# T-ShirtPress_Schematic.net
KiCad netlist of a schematic drawn in EAGLE
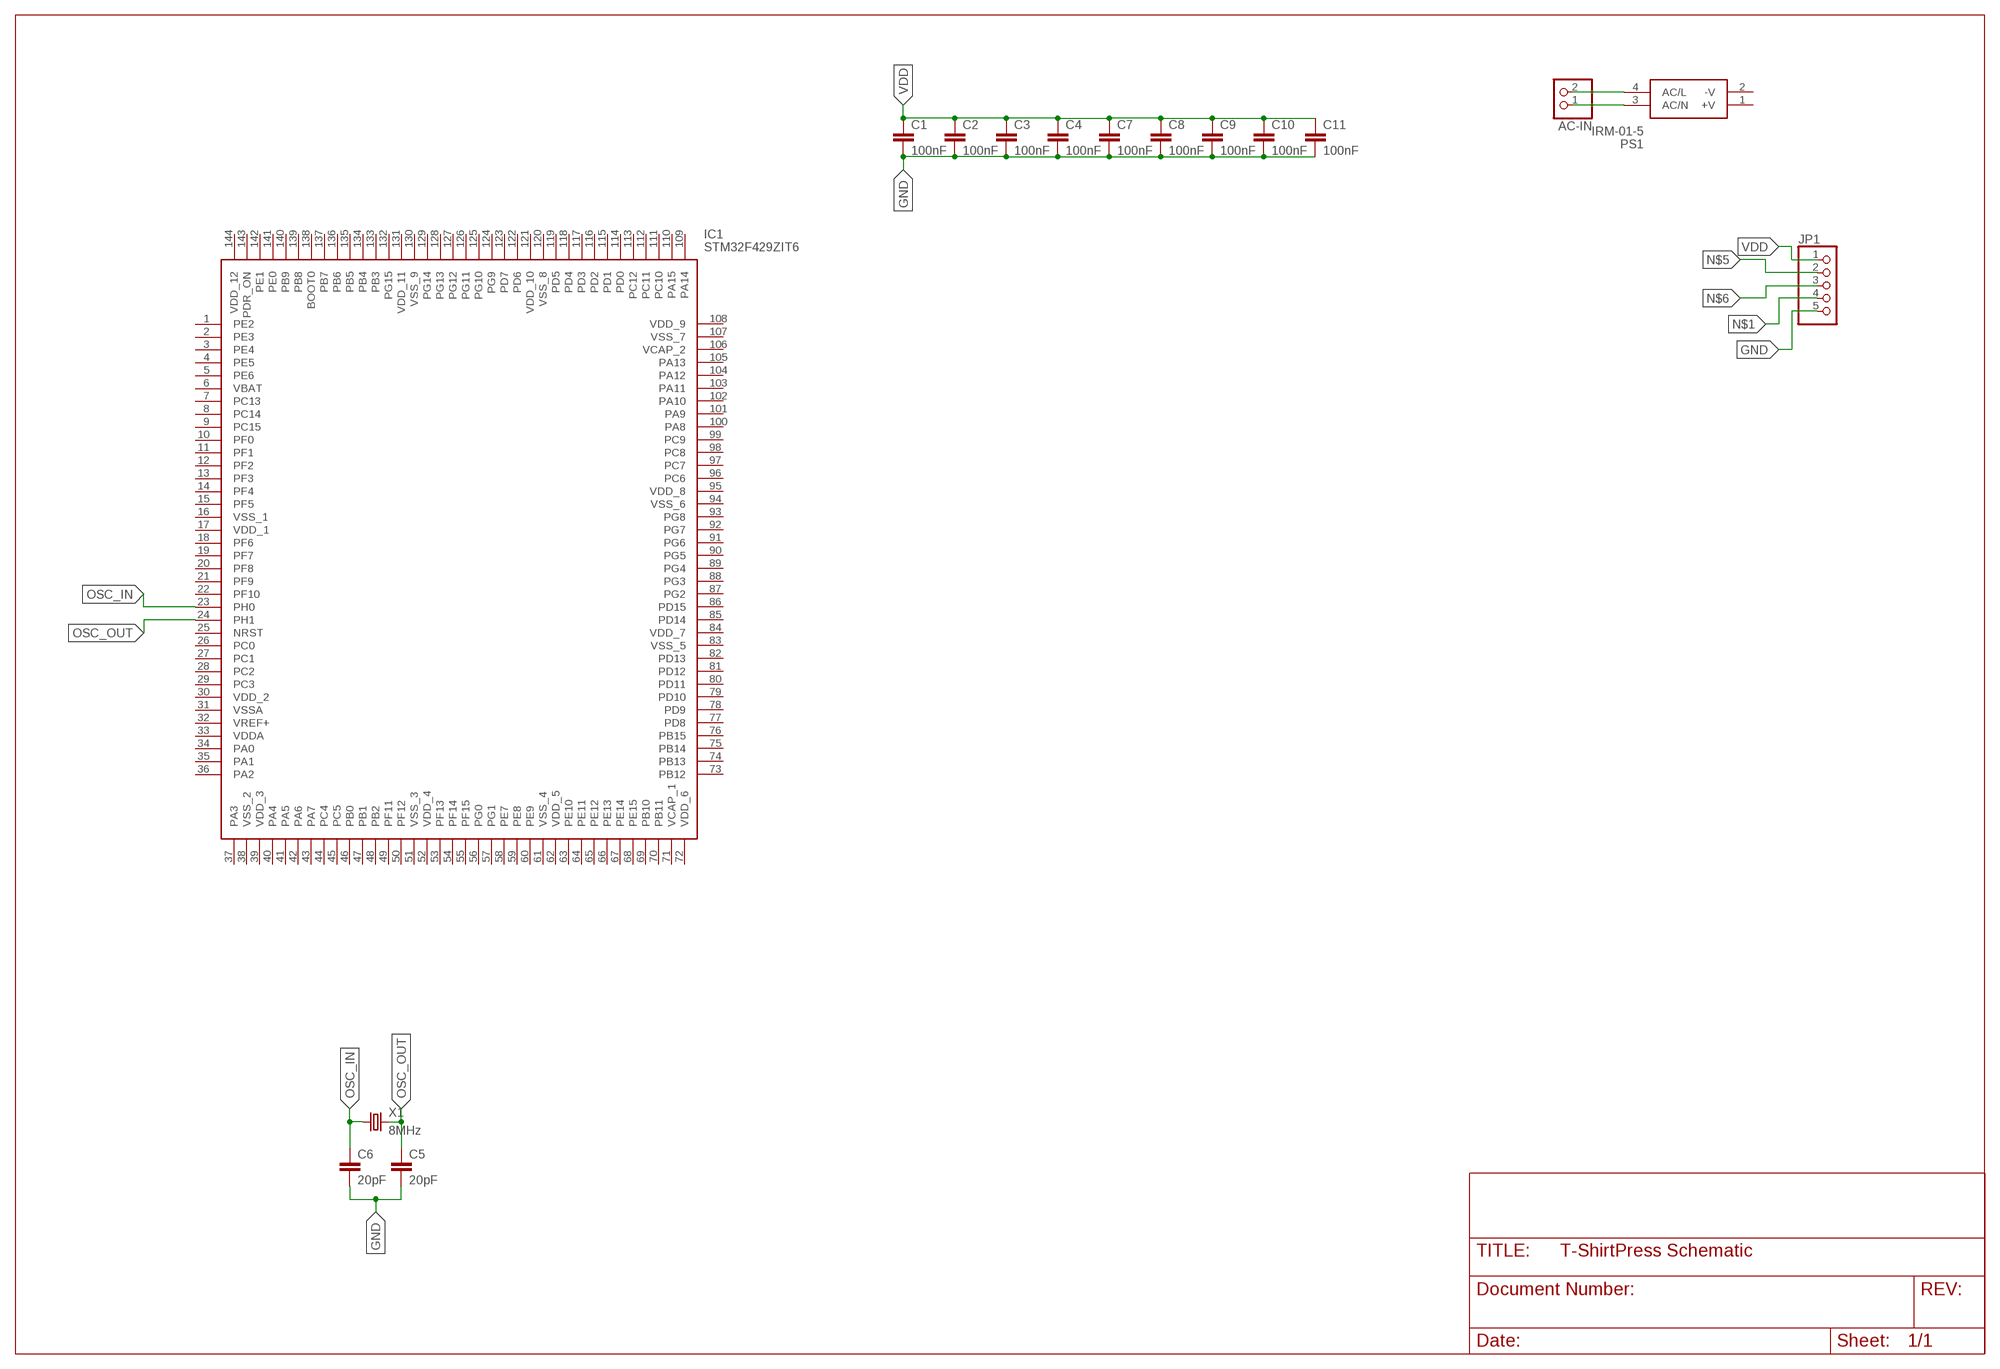
[diagram p0: schematic, sheet 1]

(export (version "E")
  (design (tool "Eeschema 10.0.6"))
  (components
    (comp (ref "AC-IN")
      (value "PINHD-1X2")
      (footprint "eagle-import:1X02")
      (libsource (lib "eagle-import") (part "PINHD-1X2"))
    )
    (comp (ref "C1")
      (value "100nF")
      (footprint "eagle-import:C1206")
      (libsource (lib "eagle-import") (part "C-EUC1206"))
    )
    (comp (ref "C2")
      (value "100nF")
      (footprint "eagle-import:C1206")
      (libsource (lib "eagle-import") (part "C-EUC1206"))
    )
    (comp (ref "C3")
      (value "100nF")
      (footprint "eagle-import:C1206")
      (libsource (lib "eagle-import") (part "C-EUC1206"))
    )
    (comp (ref "C4")
      (value "100nF")
      (footprint "eagle-import:C1206")
      (libsource (lib "eagle-import") (part "C-EUC1206"))
    )
    (comp (ref "C5")
      (value "20pF")
      (footprint "eagle-import:C1206")
      (libsource (lib "eagle-import") (part "C-EUC1206"))
    )
    (comp (ref "C6")
      (value "20pF")
      (footprint "eagle-import:C1206")
      (libsource (lib "eagle-import") (part "C-EUC1206"))
    )
    (comp (ref "C7")
      (value "100nF")
      (footprint "eagle-import:C1206")
      (libsource (lib "eagle-import") (part "C-EUC1206"))
    )
    (comp (ref "C8")
      (value "100nF")
      (footprint "eagle-import:C1206")
      (libsource (lib "eagle-import") (part "C-EUC1206"))
    )
    (comp (ref "C9")
      (value "100nF")
      (footprint "eagle-import:C1206")
      (libsource (lib "eagle-import") (part "C-EUC1206"))
    )
    (comp (ref "C10")
      (value "100nF")
      (footprint "eagle-import:C1206")
      (libsource (lib "eagle-import") (part "C-EUC1206"))
    )
    (comp (ref "C11")
      (value "100nF")
      (footprint "eagle-import:C1206")
      (libsource (lib "eagle-import") (part "C-EUC1206"))
    )
    (comp (ref "IC1")
      (value "STM32F429ZIT6")
      (footprint "eagle-import:QFP50P2200X2200X160-144N")
      (fields
        (field (name "MOUSER_PART_NUMBER") "511-STM32F429ZIT6")
        (field (name "RS_PART_NUMBER") "7926053P")
      )
      (libsource (lib "eagle-import") (part "STM32F429ZIT6"))
    )
    (comp (ref "JP1")
      (value "PINHD-1X5")
      (footprint "eagle-import:1X05")
      (libsource (lib "eagle-import") (part "PINHD-1X5"))
    )
    (comp (ref "PS1")
      (value "IRM-01-5")
      (footprint "eagle-import:IRM015")
      (fields (field (name "MOUSER_PART_NUMBER") "709-IRM01-5"))
      (libsource (lib "eagle-import") (part "IRM-01-5"))
    )
    (comp (ref "X1")
      (value "8MHz")
      (footprint "eagle-import:HC49_S")
      (libsource (lib "eagle-import") (part "CRYSTALHC49S"))
    )
  )
  (nets
    (net (code "1") (name "/VDDA") (class "Default")
      (node (ref "IC1") (pin "33") (pinfunction "VDDA_33") (pintype "power_in"))
    )
    (net (code "2") (name "/VDD_1") (class "Default")
      (node (ref "IC1") (pin "17") (pinfunction "VDD_1_17") (pintype "power_in"))
    )
    (net (code "3") (name "/VDD_2") (class "Default")
      (node (ref "IC1") (pin "30") (pinfunction "VDD_2_30") (pintype "power_in"))
    )
    (net (code "4") (name "/VDD_3") (class "Default")
      (node (ref "IC1") (pin "39") (pinfunction "VDD_3_39") (pintype "power_in"))
    )
    (net (code "5") (name "/VDD_4") (class "Default")
      (node (ref "IC1") (pin "52") (pinfunction "VDD_4_52") (pintype "power_in"))
    )
    (net (code "6") (name "/VDD_5") (class "Default")
      (node (ref "IC1") (pin "62") (pinfunction "VDD_5_62") (pintype "power_in"))
    )
    (net (code "7") (name "/VDD_6") (class "Default")
      (node (ref "IC1") (pin "72") (pinfunction "VDD_6_72") (pintype "power_in"))
    )
    (net (code "8") (name "/VDD_7") (class "Default")
      (node (ref "IC1") (pin "84") (pinfunction "VDD_7_84") (pintype "power_in"))
    )
    (net (code "9") (name "/VDD_8") (class "Default")
      (node (ref "IC1") (pin "95") (pinfunction "VDD_8_95") (pintype "power_in"))
    )
    (net (code "10") (name "/VDD_9") (class "Default")
      (node (ref "IC1") (pin "108") (pinfunction "VDD_9_108") (pintype "power_in"))
    )
    (net (code "11") (name "/VDD_10") (class "Default")
      (node (ref "IC1") (pin "121") (pinfunction "VDD_10_121") (pintype "power_in"))
    )
    (net (code "12") (name "/VDD_11") (class "Default")
      (node (ref "IC1") (pin "131") (pinfunction "VDD_11_131") (pintype "power_in"))
    )
    (net (code "13") (name "/VDD_12") (class "Default")
      (node (ref "IC1") (pin "144") (pinfunction "VDD_12_144") (pintype "power_in"))
    )
    (net (code "14") (name "/VSSA") (class "Default")
      (node (ref "IC1") (pin "31") (pinfunction "VSSA_31") (pintype "power_in"))
    )
    (net (code "15") (name "/VSS_1") (class "Default")
      (node (ref "IC1") (pin "16") (pinfunction "VSS_1_16") (pintype "power_in"))
    )
    (net (code "16") (name "/VSS_2") (class "Default")
      (node (ref "IC1") (pin "38") (pinfunction "VSS_2_38") (pintype "power_in"))
    )
    (net (code "17") (name "/VSS_3") (class "Default")
      (node (ref "IC1") (pin "51") (pinfunction "VSS_3_51") (pintype "power_in"))
    )
    (net (code "18") (name "/VSS_4") (class "Default")
      (node (ref "IC1") (pin "61") (pinfunction "VSS_4_61") (pintype "power_in"))
    )
    (net (code "19") (name "/VSS_5") (class "Default")
      (node (ref "IC1") (pin "83") (pinfunction "VSS_5_83") (pintype "power_in"))
    )
    (net (code "20") (name "/VSS_6") (class "Default")
      (node (ref "IC1") (pin "94") (pinfunction "VSS_6_94") (pintype "power_in"))
    )
    (net (code "21") (name "/VSS_7") (class "Default")
      (node (ref "IC1") (pin "107") (pinfunction "VSS_7_107") (pintype "power_in"))
    )
    (net (code "22") (name "/VSS_8") (class "Default")
      (node (ref "IC1") (pin "120") (pinfunction "VSS_8_120") (pintype "power_in"))
    )
    (net (code "23") (name "/VSS_9") (class "Default")
      (node (ref "IC1") (pin "130") (pinfunction "VSS_9_130") (pintype "power_in"))
    )
    (net (code "24") (name "GND") (class "Default")
      (node (ref "C1") (pin "2") (pinfunction "2_2") (pintype "passive"))
      (node (ref "C10") (pin "2") (pinfunction "2_2") (pintype "passive"))
      (node (ref "C11") (pin "2") (pinfunction "2_2") (pintype "passive"))
      (node (ref "C2") (pin "2") (pinfunction "2_2") (pintype "passive"))
      (node (ref "C3") (pin "2") (pinfunction "2_2") (pintype "passive"))
      (node (ref "C4") (pin "2") (pinfunction "2_2") (pintype "passive"))
      (node (ref "C5") (pin "2") (pinfunction "2_2") (pintype "passive"))
      (node (ref "C6") (pin "2") (pinfunction "2_2") (pintype "passive"))
      (node (ref "C7") (pin "2") (pinfunction "2_2") (pintype "passive"))
      (node (ref "C8") (pin "2") (pinfunction "2_2") (pintype "passive"))
      (node (ref "C9") (pin "2") (pinfunction "2_2") (pintype "passive"))
      (node (ref "JP1") (pin "5") (pinfunction "5_5") (pintype "passive"))
    )
    (net (code "25") (name "N$1") (class "Default")
      (node (ref "JP1") (pin "4") (pinfunction "4_4") (pintype "passive"))
    )
    (net (code "26") (name "N$5") (class "Default")
      (node (ref "JP1") (pin "2") (pinfunction "2_2") (pintype "passive"))
    )
    (net (code "27") (name "N$6") (class "Default")
      (node (ref "JP1") (pin "3") (pinfunction "3_3") (pintype "passive"))
    )
    (net (code "28") (name "Net-(PS1-AC{slash}L)") (class "Default")
      (node (ref "AC-IN") (pin "2") (pinfunction "2_2") (pintype "passive"))
      (node (ref "PS1") (pin "4") (pinfunction "AC/L_4") (pintype "bidirectional"))
    )
    (net (code "29") (name "Net-(PS1-AC{slash}N)") (class "Default")
      (node (ref "AC-IN") (pin "1") (pinfunction "1_1") (pintype "passive"))
      (node (ref "PS1") (pin "3") (pinfunction "AC/N_3") (pintype "bidirectional"))
    )
    (net (code "30") (name "OSC_IN") (class "Default")
      (node (ref "C6") (pin "1") (pinfunction "1_1") (pintype "passive"))
      (node (ref "IC1") (pin "23") (pinfunction "PH0_23") (pintype "bidirectional"))
      (node (ref "X1") (pin "1") (pinfunction "1_1") (pintype "passive"))
    )
    (net (code "31") (name "OSC_OUT") (class "Default")
      (node (ref "C5") (pin "1") (pinfunction "1_1") (pintype "passive"))
      (node (ref "IC1") (pin "24") (pinfunction "PH1_24") (pintype "bidirectional"))
      (node (ref "X1") (pin "2") (pinfunction "2_2") (pintype "passive"))
    )
    (net (code "32") (name "VDD") (class "Default")
      (node (ref "C1") (pin "1") (pinfunction "1_1") (pintype "passive"))
      (node (ref "C10") (pin "1") (pinfunction "1_1") (pintype "passive"))
      (node (ref "C11") (pin "1") (pinfunction "1_1") (pintype "passive"))
      (node (ref "C2") (pin "1") (pinfunction "1_1") (pintype "passive"))
      (node (ref "C3") (pin "1") (pinfunction "1_1") (pintype "passive"))
      (node (ref "C4") (pin "1") (pinfunction "1_1") (pintype "passive"))
      (node (ref "C7") (pin "1") (pinfunction "1_1") (pintype "passive"))
      (node (ref "C8") (pin "1") (pinfunction "1_1") (pintype "passive"))
      (node (ref "C9") (pin "1") (pinfunction "1_1") (pintype "passive"))
      (node (ref "JP1") (pin "1") (pinfunction "1_1") (pintype "passive"))
    )
    (net (code "33") (name "unconnected-(IC1-BOOT0-Pad138)") (class "Default")
      (node (ref "IC1") (pin "138") (pinfunction "BOOT0_138") (pintype "bidirectional"))
    )
    (net (code "34") (name "unconnected-(IC1-NRST-Pad25)") (class "Default")
      (node (ref "IC1") (pin "25") (pinfunction "NRST_25") (pintype "input"))
    )
    (net (code "35") (name "unconnected-(IC1-PA0-Pad34)") (class "Default")
      (node (ref "IC1") (pin "34") (pinfunction "PA0_34") (pintype "bidirectional"))
    )
    (net (code "36") (name "unconnected-(IC1-PA1-Pad35)") (class "Default")
      (node (ref "IC1") (pin "35") (pinfunction "PA1_35") (pintype "bidirectional"))
    )
    (net (code "37") (name "unconnected-(IC1-PA2-Pad36)") (class "Default")
      (node (ref "IC1") (pin "36") (pinfunction "PA2_36") (pintype "bidirectional"))
    )
    (net (code "38") (name "unconnected-(IC1-PA3-Pad37)") (class "Default")
      (node (ref "IC1") (pin "37") (pinfunction "PA3_37") (pintype "bidirectional"))
    )
    (net (code "39") (name "unconnected-(IC1-PA4-Pad40)") (class "Default")
      (node (ref "IC1") (pin "40") (pinfunction "PA4_40") (pintype "bidirectional"))
    )
    (net (code "40") (name "unconnected-(IC1-PA5-Pad41)") (class "Default")
      (node (ref "IC1") (pin "41") (pinfunction "PA5_41") (pintype "bidirectional"))
    )
    (net (code "41") (name "unconnected-(IC1-PA6-Pad42)") (class "Default")
      (node (ref "IC1") (pin "42") (pinfunction "PA6_42") (pintype "bidirectional"))
    )
    (net (code "42") (name "unconnected-(IC1-PA7-Pad43)") (class "Default")
      (node (ref "IC1") (pin "43") (pinfunction "PA7_43") (pintype "bidirectional"))
    )
    (net (code "43") (name "unconnected-(IC1-PA8-Pad100)") (class "Default")
      (node (ref "IC1") (pin "100") (pinfunction "PA8_100") (pintype "bidirectional"))
    )
    (net (code "44") (name "unconnected-(IC1-PA9-Pad101)") (class "Default")
      (node (ref "IC1") (pin "101") (pinfunction "PA9_101") (pintype "bidirectional"))
    )
    (net (code "45") (name "unconnected-(IC1-PA10-Pad102)") (class "Default")
      (node (ref "IC1") (pin "102") (pinfunction "PA10_102") (pintype "bidirectional"))
    )
    (net (code "46") (name "unconnected-(IC1-PA11-Pad103)") (class "Default")
      (node (ref "IC1") (pin "103") (pinfunction "PA11_103") (pintype "bidirectional"))
    )
    (net (code "47") (name "unconnected-(IC1-PA12-Pad104)") (class "Default")
      (node (ref "IC1") (pin "104") (pinfunction "PA12_104") (pintype "bidirectional"))
    )
    (net (code "48") (name "unconnected-(IC1-PA13-Pad105)") (class "Default")
      (node (ref "IC1") (pin "105") (pinfunction "PA13_105") (pintype "bidirectional"))
    )
    (net (code "49") (name "unconnected-(IC1-PA14-Pad109)") (class "Default")
      (node (ref "IC1") (pin "109") (pinfunction "PA14_109") (pintype "bidirectional"))
    )
    (net (code "50") (name "unconnected-(IC1-PA15-Pad110)") (class "Default")
      (node (ref "IC1") (pin "110") (pinfunction "PA15_110") (pintype "bidirectional"))
    )
    (net (code "51") (name "unconnected-(IC1-PB0-Pad46)") (class "Default")
      (node (ref "IC1") (pin "46") (pinfunction "PB0_46") (pintype "bidirectional"))
    )
    (net (code "52") (name "unconnected-(IC1-PB1-Pad47)") (class "Default")
      (node (ref "IC1") (pin "47") (pinfunction "PB1_47") (pintype "bidirectional"))
    )
    (net (code "53") (name "unconnected-(IC1-PB2-Pad48)") (class "Default")
      (node (ref "IC1") (pin "48") (pinfunction "PB2_48") (pintype "bidirectional"))
    )
    (net (code "54") (name "unconnected-(IC1-PB3-Pad133)") (class "Default")
      (node (ref "IC1") (pin "133") (pinfunction "PB3_133") (pintype "bidirectional"))
    )
    (net (code "55") (name "unconnected-(IC1-PB4-Pad134)") (class "Default")
      (node (ref "IC1") (pin "134") (pinfunction "PB4_134") (pintype "bidirectional"))
    )
    (net (code "56") (name "unconnected-(IC1-PB5-Pad135)") (class "Default")
      (node (ref "IC1") (pin "135") (pinfunction "PB5_135") (pintype "bidirectional"))
    )
    (net (code "57") (name "unconnected-(IC1-PB6-Pad136)") (class "Default")
      (node (ref "IC1") (pin "136") (pinfunction "PB6_136") (pintype "bidirectional"))
    )
    (net (code "58") (name "unconnected-(IC1-PB7-Pad137)") (class "Default")
      (node (ref "IC1") (pin "137") (pinfunction "PB7_137") (pintype "bidirectional"))
    )
    (net (code "59") (name "unconnected-(IC1-PB8-Pad139)") (class "Default")
      (node (ref "IC1") (pin "139") (pinfunction "PB8_139") (pintype "bidirectional"))
    )
    (net (code "60") (name "unconnected-(IC1-PB9-Pad140)") (class "Default")
      (node (ref "IC1") (pin "140") (pinfunction "PB9_140") (pintype "bidirectional"))
    )
    (net (code "61") (name "unconnected-(IC1-PB10-Pad69)") (class "Default")
      (node (ref "IC1") (pin "69") (pinfunction "PB10_69") (pintype "bidirectional"))
    )
    (net (code "62") (name "unconnected-(IC1-PB11-Pad70)") (class "Default")
      (node (ref "IC1") (pin "70") (pinfunction "PB11_70") (pintype "bidirectional"))
    )
    (net (code "63") (name "unconnected-(IC1-PB12-Pad73)") (class "Default")
      (node (ref "IC1") (pin "73") (pinfunction "PB12_73") (pintype "bidirectional"))
    )
    (net (code "64") (name "unconnected-(IC1-PB13-Pad74)") (class "Default")
      (node (ref "IC1") (pin "74") (pinfunction "PB13_74") (pintype "bidirectional"))
    )
    (net (code "65") (name "unconnected-(IC1-PB14-Pad75)") (class "Default")
      (node (ref "IC1") (pin "75") (pinfunction "PB14_75") (pintype "bidirectional"))
    )
    (net (code "66") (name "unconnected-(IC1-PB15-Pad76)") (class "Default")
      (node (ref "IC1") (pin "76") (pinfunction "PB15_76") (pintype "bidirectional"))
    )
    (net (code "67") (name "unconnected-(IC1-PC0-Pad26)") (class "Default")
      (node (ref "IC1") (pin "26") (pinfunction "PC0_26") (pintype "bidirectional"))
    )
    (net (code "68") (name "unconnected-(IC1-PC1-Pad27)") (class "Default")
      (node (ref "IC1") (pin "27") (pinfunction "PC1_27") (pintype "bidirectional"))
    )
    (net (code "69") (name "unconnected-(IC1-PC2-Pad28)") (class "Default")
      (node (ref "IC1") (pin "28") (pinfunction "PC2_28") (pintype "bidirectional"))
    )
    (net (code "70") (name "unconnected-(IC1-PC3-Pad29)") (class "Default")
      (node (ref "IC1") (pin "29") (pinfunction "PC3_29") (pintype "bidirectional"))
    )
    (net (code "71") (name "unconnected-(IC1-PC4-Pad44)") (class "Default")
      (node (ref "IC1") (pin "44") (pinfunction "PC4_44") (pintype "bidirectional"))
    )
    (net (code "72") (name "unconnected-(IC1-PC5-Pad45)") (class "Default")
      (node (ref "IC1") (pin "45") (pinfunction "PC5_45") (pintype "bidirectional"))
    )
    (net (code "73") (name "unconnected-(IC1-PC6-Pad96)") (class "Default")
      (node (ref "IC1") (pin "96") (pinfunction "PC6_96") (pintype "bidirectional"))
    )
    (net (code "74") (name "unconnected-(IC1-PC7-Pad97)") (class "Default")
      (node (ref "IC1") (pin "97") (pinfunction "PC7_97") (pintype "bidirectional"))
    )
    (net (code "75") (name "unconnected-(IC1-PC8-Pad98)") (class "Default")
      (node (ref "IC1") (pin "98") (pinfunction "PC8_98") (pintype "bidirectional"))
    )
    (net (code "76") (name "unconnected-(IC1-PC9-Pad99)") (class "Default")
      (node (ref "IC1") (pin "99") (pinfunction "PC9_99") (pintype "bidirectional"))
    )
    (net (code "77") (name "unconnected-(IC1-PC10-Pad111)") (class "Default")
      (node (ref "IC1") (pin "111") (pinfunction "PC10_111") (pintype "bidirectional"))
    )
    (net (code "78") (name "unconnected-(IC1-PC11-Pad112)") (class "Default")
      (node (ref "IC1") (pin "112") (pinfunction "PC11_112") (pintype "bidirectional"))
    )
    (net (code "79") (name "unconnected-(IC1-PC12-Pad113)") (class "Default")
      (node (ref "IC1") (pin "113") (pinfunction "PC12_113") (pintype "bidirectional"))
    )
    (net (code "80") (name "unconnected-(IC1-PC13-Pad7)") (class "Default")
      (node (ref "IC1") (pin "7") (pinfunction "PC13_7") (pintype "bidirectional"))
    )
    (net (code "81") (name "unconnected-(IC1-PC14-Pad8)") (class "Default")
      (node (ref "IC1") (pin "8") (pinfunction "PC14_8") (pintype "bidirectional"))
    )
    (net (code "82") (name "unconnected-(IC1-PC15-Pad9)") (class "Default")
      (node (ref "IC1") (pin "9") (pinfunction "PC15_9") (pintype "bidirectional"))
    )
    (net (code "83") (name "unconnected-(IC1-PD0-Pad114)") (class "Default")
      (node (ref "IC1") (pin "114") (pinfunction "PD0_114") (pintype "bidirectional"))
    )
    (net (code "84") (name "unconnected-(IC1-PD1-Pad115)") (class "Default")
      (node (ref "IC1") (pin "115") (pinfunction "PD1_115") (pintype "bidirectional"))
    )
    (net (code "85") (name "unconnected-(IC1-PD2-Pad116)") (class "Default")
      (node (ref "IC1") (pin "116") (pinfunction "PD2_116") (pintype "bidirectional"))
    )
    (net (code "86") (name "unconnected-(IC1-PD3-Pad117)") (class "Default")
      (node (ref "IC1") (pin "117") (pinfunction "PD3_117") (pintype "bidirectional"))
    )
    (net (code "87") (name "unconnected-(IC1-PD4-Pad118)") (class "Default")
      (node (ref "IC1") (pin "118") (pinfunction "PD4_118") (pintype "bidirectional"))
    )
    (net (code "88") (name "unconnected-(IC1-PD5-Pad119)") (class "Default")
      (node (ref "IC1") (pin "119") (pinfunction "PD5_119") (pintype "bidirectional"))
    )
    (net (code "89") (name "unconnected-(IC1-PD6-Pad122)") (class "Default")
      (node (ref "IC1") (pin "122") (pinfunction "PD6_122") (pintype "bidirectional"))
    )
    (net (code "90") (name "unconnected-(IC1-PD7-Pad123)") (class "Default")
      (node (ref "IC1") (pin "123") (pinfunction "PD7_123") (pintype "bidirectional"))
    )
    (net (code "91") (name "unconnected-(IC1-PD8-Pad77)") (class "Default")
      (node (ref "IC1") (pin "77") (pinfunction "PD8_77") (pintype "bidirectional"))
    )
    (net (code "92") (name "unconnected-(IC1-PD9-Pad78)") (class "Default")
      (node (ref "IC1") (pin "78") (pinfunction "PD9_78") (pintype "bidirectional"))
    )
    (net (code "93") (name "unconnected-(IC1-PD10-Pad79)") (class "Default")
      (node (ref "IC1") (pin "79") (pinfunction "PD10_79") (pintype "bidirectional"))
    )
    (net (code "94") (name "unconnected-(IC1-PD11-Pad80)") (class "Default")
      (node (ref "IC1") (pin "80") (pinfunction "PD11_80") (pintype "bidirectional"))
    )
    (net (code "95") (name "unconnected-(IC1-PD12-Pad81)") (class "Default")
      (node (ref "IC1") (pin "81") (pinfunction "PD12_81") (pintype "bidirectional"))
    )
    (net (code "96") (name "unconnected-(IC1-PD13-Pad82)") (class "Default")
      (node (ref "IC1") (pin "82") (pinfunction "PD13_82") (pintype "bidirectional"))
    )
    (net (code "97") (name "unconnected-(IC1-PD14-Pad85)") (class "Default")
      (node (ref "IC1") (pin "85") (pinfunction "PD14_85") (pintype "bidirectional"))
    )
    (net (code "98") (name "unconnected-(IC1-PD15-Pad86)") (class "Default")
      (node (ref "IC1") (pin "86") (pinfunction "PD15_86") (pintype "bidirectional"))
    )
    (net (code "99") (name "unconnected-(IC1-PDR_ON-Pad143)") (class "Default")
      (node (ref "IC1") (pin "143") (pinfunction "PDR_ON_143") (pintype "bidirectional"))
    )
    (net (code "100") (name "unconnected-(IC1-PE0-Pad141)") (class "Default")
      (node (ref "IC1") (pin "141") (pinfunction "PE0_141") (pintype "bidirectional"))
    )
    (net (code "101") (name "unconnected-(IC1-PE1-Pad142)") (class "Default")
      (node (ref "IC1") (pin "142") (pinfunction "PE1_142") (pintype "bidirectional"))
    )
    (net (code "102") (name "unconnected-(IC1-PE2-Pad1)") (class "Default")
      (node (ref "IC1") (pin "1") (pinfunction "PE2_1") (pintype "bidirectional"))
    )
    (net (code "103") (name "unconnected-(IC1-PE3-Pad2)") (class "Default")
      (node (ref "IC1") (pin "2") (pinfunction "PE3_2") (pintype "bidirectional"))
    )
    (net (code "104") (name "unconnected-(IC1-PE4-Pad3)") (class "Default")
      (node (ref "IC1") (pin "3") (pinfunction "PE4_3") (pintype "bidirectional"))
    )
    (net (code "105") (name "unconnected-(IC1-PE5-Pad4)") (class "Default")
      (node (ref "IC1") (pin "4") (pinfunction "PE5_4") (pintype "bidirectional"))
    )
    (net (code "106") (name "unconnected-(IC1-PE6-Pad5)") (class "Default")
      (node (ref "IC1") (pin "5") (pinfunction "PE6_5") (pintype "bidirectional"))
    )
    (net (code "107") (name "unconnected-(IC1-PE7-Pad58)") (class "Default")
      (node (ref "IC1") (pin "58") (pinfunction "PE7_58") (pintype "bidirectional"))
    )
    (net (code "108") (name "unconnected-(IC1-PE8-Pad59)") (class "Default")
      (node (ref "IC1") (pin "59") (pinfunction "PE8_59") (pintype "bidirectional"))
    )
    (net (code "109") (name "unconnected-(IC1-PE9-Pad60)") (class "Default")
      (node (ref "IC1") (pin "60") (pinfunction "PE9_60") (pintype "bidirectional"))
    )
    (net (code "110") (name "unconnected-(IC1-PE10-Pad63)") (class "Default")
      (node (ref "IC1") (pin "63") (pinfunction "PE10_63") (pintype "bidirectional"))
    )
    (net (code "111") (name "unconnected-(IC1-PE11-Pad64)") (class "Default")
      (node (ref "IC1") (pin "64") (pinfunction "PE11_64") (pintype "bidirectional"))
    )
    (net (code "112") (name "unconnected-(IC1-PE12-Pad65)") (class "Default")
      (node (ref "IC1") (pin "65") (pinfunction "PE12_65") (pintype "bidirectional"))
    )
    (net (code "113") (name "unconnected-(IC1-PE13-Pad66)") (class "Default")
      (node (ref "IC1") (pin "66") (pinfunction "PE13_66") (pintype "bidirectional"))
    )
    (net (code "114") (name "unconnected-(IC1-PE14-Pad67)") (class "Default")
      (node (ref "IC1") (pin "67") (pinfunction "PE14_67") (pintype "bidirectional"))
    )
    (net (code "115") (name "unconnected-(IC1-PE15-Pad68)") (class "Default")
      (node (ref "IC1") (pin "68") (pinfunction "PE15_68") (pintype "bidirectional"))
    )
    (net (code "116") (name "unconnected-(IC1-PF0-Pad10)") (class "Default")
      (node (ref "IC1") (pin "10") (pinfunction "PF0_10") (pintype "bidirectional"))
    )
    (net (code "117") (name "unconnected-(IC1-PF1-Pad11)") (class "Default")
      (node (ref "IC1") (pin "11") (pinfunction "PF1_11") (pintype "bidirectional"))
    )
    (net (code "118") (name "unconnected-(IC1-PF2-Pad12)") (class "Default")
      (node (ref "IC1") (pin "12") (pinfunction "PF2_12") (pintype "bidirectional"))
    )
    (net (code "119") (name "unconnected-(IC1-PF3-Pad13)") (class "Default")
      (node (ref "IC1") (pin "13") (pinfunction "PF3_13") (pintype "bidirectional"))
    )
    (net (code "120") (name "unconnected-(IC1-PF4-Pad14)") (class "Default")
      (node (ref "IC1") (pin "14") (pinfunction "PF4_14") (pintype "bidirectional"))
    )
    (net (code "121") (name "unconnected-(IC1-PF5-Pad15)") (class "Default")
      (node (ref "IC1") (pin "15") (pinfunction "PF5_15") (pintype "bidirectional"))
    )
    (net (code "122") (name "unconnected-(IC1-PF6-Pad18)") (class "Default")
      (node (ref "IC1") (pin "18") (pinfunction "PF6_18") (pintype "bidirectional"))
    )
    (net (code "123") (name "unconnected-(IC1-PF7-Pad19)") (class "Default")
      (node (ref "IC1") (pin "19") (pinfunction "PF7_19") (pintype "bidirectional"))
    )
    (net (code "124") (name "unconnected-(IC1-PF8-Pad20)") (class "Default")
      (node (ref "IC1") (pin "20") (pinfunction "PF8_20") (pintype "bidirectional"))
    )
    (net (code "125") (name "unconnected-(IC1-PF9-Pad21)") (class "Default")
      (node (ref "IC1") (pin "21") (pinfunction "PF9_21") (pintype "bidirectional"))
    )
    (net (code "126") (name "unconnected-(IC1-PF10-Pad22)") (class "Default")
      (node (ref "IC1") (pin "22") (pinfunction "PF10_22") (pintype "bidirectional"))
    )
    (net (code "127") (name "unconnected-(IC1-PF11-Pad49)") (class "Default")
      (node (ref "IC1") (pin "49") (pinfunction "PF11_49") (pintype "bidirectional"))
    )
    (net (code "128") (name "unconnected-(IC1-PF12-Pad50)") (class "Default")
      (node (ref "IC1") (pin "50") (pinfunction "PF12_50") (pintype "bidirectional"))
    )
    (net (code "129") (name "unconnected-(IC1-PF13-Pad53)") (class "Default")
      (node (ref "IC1") (pin "53") (pinfunction "PF13_53") (pintype "bidirectional"))
    )
    (net (code "130") (name "unconnected-(IC1-PF14-Pad54)") (class "Default")
      (node (ref "IC1") (pin "54") (pinfunction "PF14_54") (pintype "bidirectional"))
    )
    (net (code "131") (name "unconnected-(IC1-PF15-Pad55)") (class "Default")
      (node (ref "IC1") (pin "55") (pinfunction "PF15_55") (pintype "bidirectional"))
    )
    (net (code "132") (name "unconnected-(IC1-PG0-Pad56)") (class "Default")
      (node (ref "IC1") (pin "56") (pinfunction "PG0_56") (pintype "bidirectional"))
    )
    (net (code "133") (name "unconnected-(IC1-PG1-Pad57)") (class "Default")
      (node (ref "IC1") (pin "57") (pinfunction "PG1_57") (pintype "bidirectional"))
    )
    (net (code "134") (name "unconnected-(IC1-PG2-Pad87)") (class "Default")
      (node (ref "IC1") (pin "87") (pinfunction "PG2_87") (pintype "bidirectional"))
    )
    (net (code "135") (name "unconnected-(IC1-PG3-Pad88)") (class "Default")
      (node (ref "IC1") (pin "88") (pinfunction "PG3_88") (pintype "bidirectional"))
    )
    (net (code "136") (name "unconnected-(IC1-PG4-Pad89)") (class "Default")
      (node (ref "IC1") (pin "89") (pinfunction "PG4_89") (pintype "bidirectional"))
    )
    (net (code "137") (name "unconnected-(IC1-PG5-Pad90)") (class "Default")
      (node (ref "IC1") (pin "90") (pinfunction "PG5_90") (pintype "bidirectional"))
    )
    (net (code "138") (name "unconnected-(IC1-PG6-Pad91)") (class "Default")
      (node (ref "IC1") (pin "91") (pinfunction "PG6_91") (pintype "bidirectional"))
    )
    (net (code "139") (name "unconnected-(IC1-PG7-Pad92)") (class "Default")
      (node (ref "IC1") (pin "92") (pinfunction "PG7_92") (pintype "bidirectional"))
    )
    (net (code "140") (name "unconnected-(IC1-PG8-Pad93)") (class "Default")
      (node (ref "IC1") (pin "93") (pinfunction "PG8_93") (pintype "bidirectional"))
    )
    (net (code "141") (name "unconnected-(IC1-PG9-Pad124)") (class "Default")
      (node (ref "IC1") (pin "124") (pinfunction "PG9_124") (pintype "bidirectional"))
    )
    (net (code "142") (name "unconnected-(IC1-PG10-Pad125)") (class "Default")
      (node (ref "IC1") (pin "125") (pinfunction "PG10_125") (pintype "bidirectional"))
    )
    (net (code "143") (name "unconnected-(IC1-PG11-Pad126)") (class "Default")
      (node (ref "IC1") (pin "126") (pinfunction "PG11_126") (pintype "bidirectional"))
    )
    (net (code "144") (name "unconnected-(IC1-PG12-Pad127)") (class "Default")
      (node (ref "IC1") (pin "127") (pinfunction "PG12_127") (pintype "bidirectional"))
    )
    (net (code "145") (name "unconnected-(IC1-PG13-Pad128)") (class "Default")
      (node (ref "IC1") (pin "128") (pinfunction "PG13_128") (pintype "bidirectional"))
    )
    (net (code "146") (name "unconnected-(IC1-PG14-Pad129)") (class "Default")
      (node (ref "IC1") (pin "129") (pinfunction "PG14_129") (pintype "bidirectional"))
    )
    (net (code "147") (name "unconnected-(IC1-PG15-Pad132)") (class "Default")
      (node (ref "IC1") (pin "132") (pinfunction "PG15_132") (pintype "bidirectional"))
    )
    (net (code "148") (name "unconnected-(IC1-VBAT-Pad6)") (class "Default")
      (node (ref "IC1") (pin "6") (pinfunction "VBAT_6") (pintype "bidirectional"))
    )
    (net (code "149") (name "unconnected-(IC1-VCAP_1-Pad71)") (class "Default")
      (node (ref "IC1") (pin "71") (pinfunction "VCAP_1_71") (pintype "bidirectional"))
    )
    (net (code "150") (name "unconnected-(IC1-VCAP_2-Pad106)") (class "Default")
      (node (ref "IC1") (pin "106") (pinfunction "VCAP_2_106") (pintype "bidirectional"))
    )
    (net (code "151") (name "unconnected-(IC1-VREF+-Pad32)") (class "Default")
      (node (ref "IC1") (pin "32") (pinfunction "VREF+_32") (pintype "input"))
    )
    (net (code "152") (name "unconnected-(PS1-+V-Pad1)") (class "Default")
      (node (ref "PS1") (pin "1") (pinfunction "+V_1") (pintype "bidirectional"))
    )
    (net (code "153") (name "unconnected-(PS1--V-Pad2)") (class "Default")
      (node (ref "PS1") (pin "2") (pinfunction "-V_2") (pintype "bidirectional"))
    )
  )
)
